# binarybox.net
KiCad netlist of a schematic drawn in EAGLE
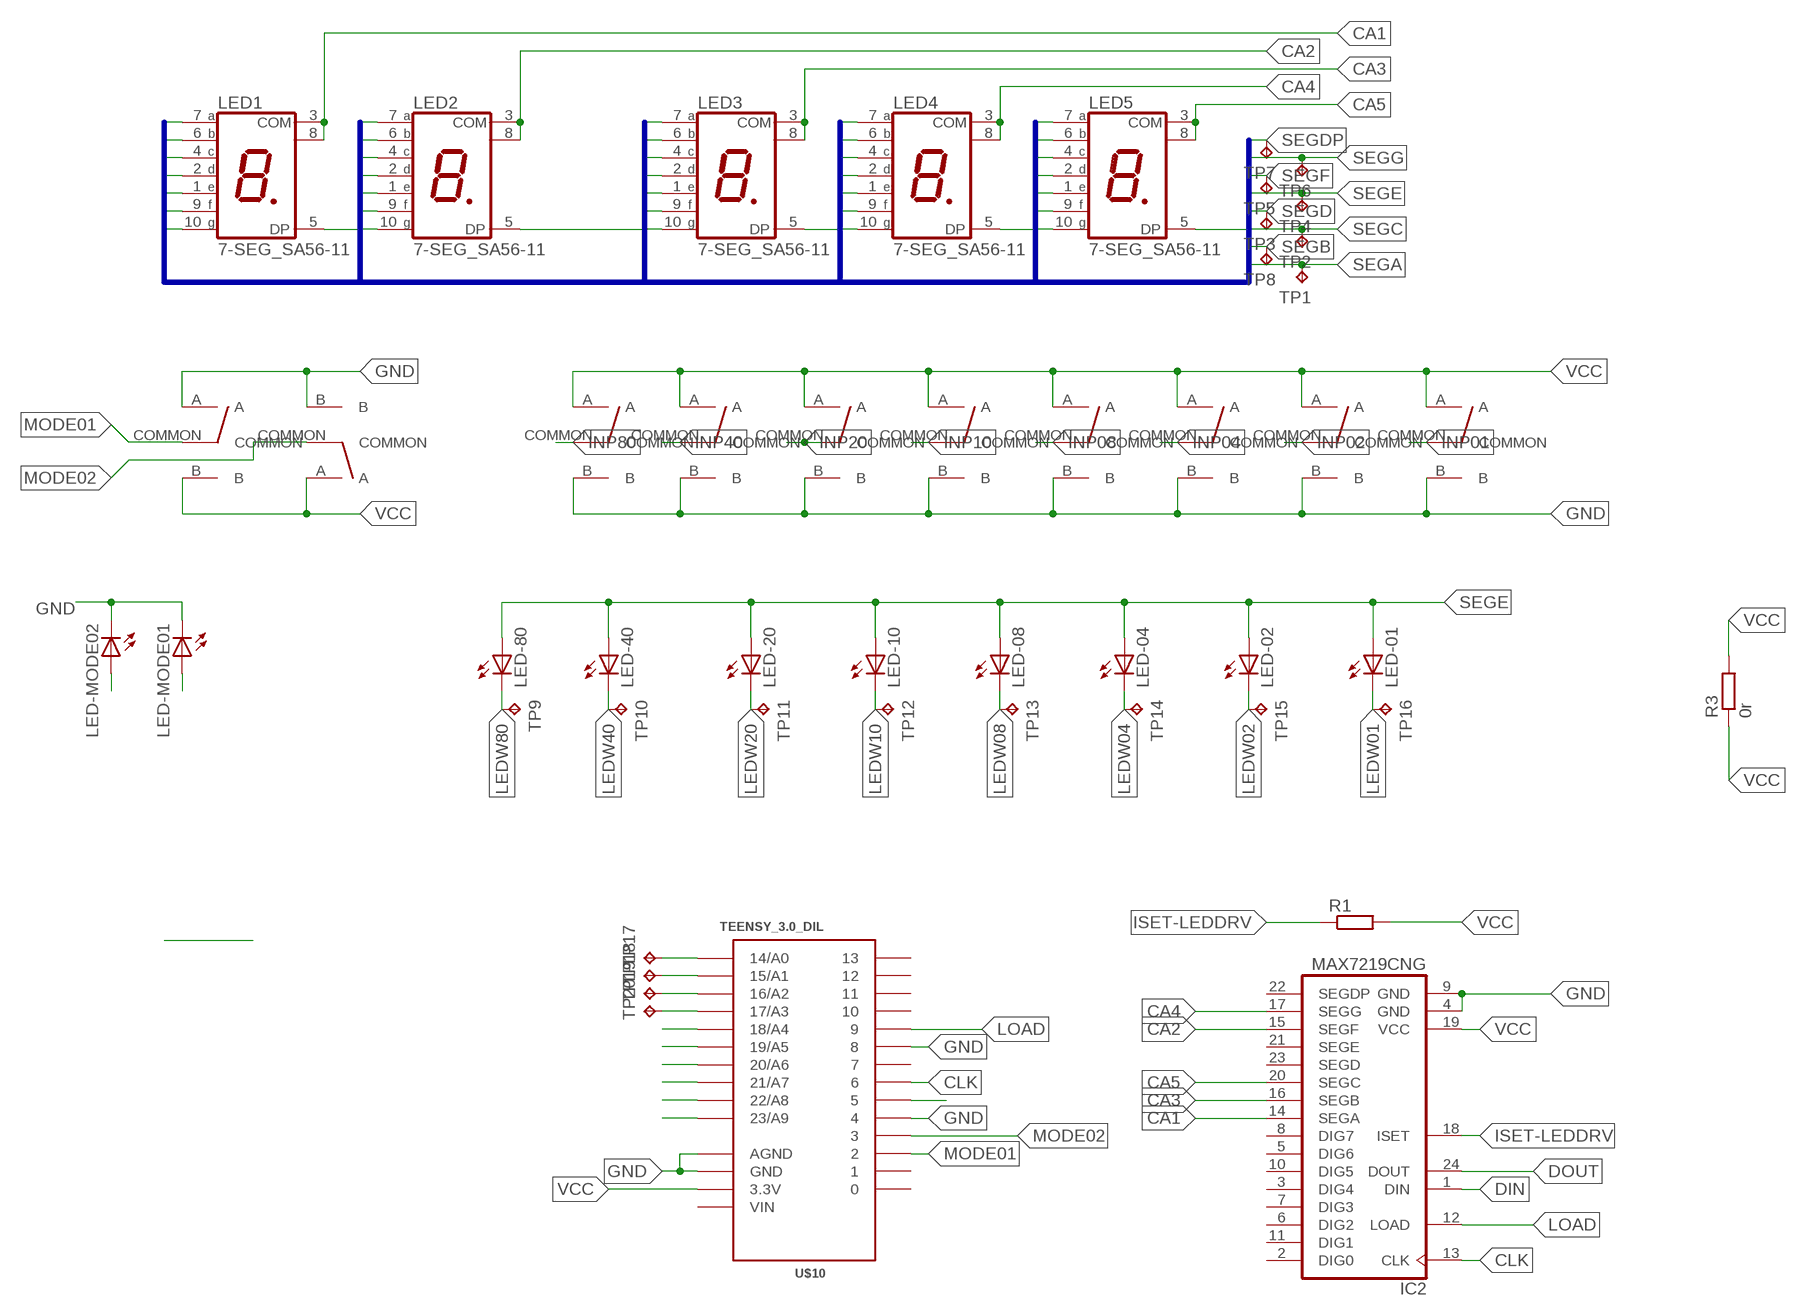
[diagram p0: schematic, sheet 1]

(export (version "E")
  (design (tool "Eeschema 10.0.6"))
  (components
    (comp (ref "IC2")
      (value "MAX7219CNG")
      (footprint "eagle-import:DIL24-3")
      (fields (field (name "MF") "MAXIM"))
      (libsource (lib "eagle-import") (part "MAX7219CNG"))
    )
    (comp (ref "LED-01")
      (value "LED5MM")
      (footprint "eagle-import:LED5MM")
      (libsource (lib "eagle-import") (part "LED5MM"))
    )
    (comp (ref "LED-02")
      (value "LED5MM")
      (footprint "eagle-import:LED5MM")
      (libsource (lib "eagle-import") (part "LED5MM"))
    )
    (comp (ref "LED-04")
      (value "LED5MM")
      (footprint "eagle-import:LED5MM")
      (libsource (lib "eagle-import") (part "LED5MM"))
    )
    (comp (ref "LED-08")
      (value "LED5MM")
      (footprint "eagle-import:LED5MM")
      (libsource (lib "eagle-import") (part "LED5MM"))
    )
    (comp (ref "LED-10")
      (value "LED5MM")
      (footprint "eagle-import:LED5MM")
      (libsource (lib "eagle-import") (part "LED5MM"))
    )
    (comp (ref "LED-20")
      (value "LED5MM")
      (footprint "eagle-import:LED5MM")
      (libsource (lib "eagle-import") (part "LED5MM"))
    )
    (comp (ref "LED-40")
      (value "LED5MM")
      (footprint "eagle-import:LED5MM")
      (libsource (lib "eagle-import") (part "LED5MM"))
    )
    (comp (ref "LED-80")
      (value "LED5MM")
      (footprint "eagle-import:LED5MM")
      (libsource (lib "eagle-import") (part "LED5MM"))
    )
    (comp (ref "LED-MODE01")
      (value "LED5MM")
      (footprint "eagle-import:LED5MM")
      (libsource (lib "eagle-import") (part "LED5MM"))
    )
    (comp (ref "LED-MODE02")
      (value "LED5MM")
      (footprint "eagle-import:LED5MM")
      (libsource (lib "eagle-import") (part "LED5MM"))
    )
    (comp (ref "LED1")
      (value "7-SEG_SA56-11")
      (footprint "eagle-import:SA56-11")
      (libsource (lib "eagle-import") (part "7-SEG_SA56-11"))
    )
    (comp (ref "LED2")
      (value "7-SEG_SA56-11")
      (footprint "eagle-import:SA56-11")
      (libsource (lib "eagle-import") (part "7-SEG_SA56-11"))
    )
    (comp (ref "LED3")
      (value "7-SEG_SA56-11")
      (footprint "eagle-import:SA56-11")
      (libsource (lib "eagle-import") (part "7-SEG_SA56-11"))
    )
    (comp (ref "LED4")
      (value "7-SEG_SA56-11")
      (footprint "eagle-import:SA56-11")
      (libsource (lib "eagle-import") (part "7-SEG_SA56-11"))
    )
    (comp (ref "LED5")
      (value "7-SEG_SA56-11")
      (footprint "eagle-import:SA56-11")
      (libsource (lib "eagle-import") (part "7-SEG_SA56-11"))
    )
    (comp (ref "R1")
      (value "R-EU_0207/10")
      (footprint "eagle-import:0207_10")
      (libsource (lib "eagle-import") (part "R-EU_0207/10"))
    )
    (comp (ref "R3")
      (value "0r")
      (footprint "eagle-import:0207_10")
      (libsource (lib "eagle-import") (part "R-EU_0207/10"))
    )
    (comp (ref "TP1")
      (value "TPB1,27")
      (footprint "eagle-import:B1,27")
      (libsource (lib "eagle-import") (part "TPB1,27"))
    )
    (comp (ref "TP2")
      (value "TPB1,27")
      (footprint "eagle-import:B1,27")
      (libsource (lib "eagle-import") (part "TPB1,27"))
    )
    (comp (ref "TP3")
      (value "TPB1,27")
      (footprint "eagle-import:B1,27")
      (libsource (lib "eagle-import") (part "TPB1,27"))
    )
    (comp (ref "TP4")
      (value "TPB1,27")
      (footprint "eagle-import:B1,27")
      (libsource (lib "eagle-import") (part "TPB1,27"))
    )
    (comp (ref "TP5")
      (value "TPB1,27")
      (footprint "eagle-import:B1,27")
      (libsource (lib "eagle-import") (part "TPB1,27"))
    )
    (comp (ref "TP6")
      (value "TPB1,27")
      (footprint "eagle-import:B1,27")
      (libsource (lib "eagle-import") (part "TPB1,27"))
    )
    (comp (ref "TP7")
      (value "TPB1,27")
      (footprint "eagle-import:B1,27")
      (libsource (lib "eagle-import") (part "TPB1,27"))
    )
    (comp (ref "TP8")
      (value "TPB1,27")
      (footprint "eagle-import:B1,27")
      (libsource (lib "eagle-import") (part "TPB1,27"))
    )
    (comp (ref "TP9")
      (value "TPB1,27")
      (footprint "eagle-import:B1,27")
      (libsource (lib "eagle-import") (part "TPB1,27"))
    )
    (comp (ref "TP10")
      (value "TPB1,27")
      (footprint "eagle-import:B1,27")
      (libsource (lib "eagle-import") (part "TPB1,27"))
    )
    (comp (ref "TP11")
      (value "TPB1,27")
      (footprint "eagle-import:B1,27")
      (libsource (lib "eagle-import") (part "TPB1,27"))
    )
    (comp (ref "TP12")
      (value "TPB1,27")
      (footprint "eagle-import:B1,27")
      (libsource (lib "eagle-import") (part "TPB1,27"))
    )
    (comp (ref "TP13")
      (value "TPB1,27")
      (footprint "eagle-import:B1,27")
      (libsource (lib "eagle-import") (part "TPB1,27"))
    )
    (comp (ref "TP14")
      (value "TPB1,27")
      (footprint "eagle-import:B1,27")
      (libsource (lib "eagle-import") (part "TPB1,27"))
    )
    (comp (ref "TP15")
      (value "TPB1,27")
      (footprint "eagle-import:B1,27")
      (libsource (lib "eagle-import") (part "TPB1,27"))
    )
    (comp (ref "TP16")
      (value "TPB1,27")
      (footprint "eagle-import:B1,27")
      (libsource (lib "eagle-import") (part "TPB1,27"))
    )
    (comp (ref "TP17")
      (value "TPB1,27")
      (footprint "eagle-import:B1,27")
      (libsource (lib "eagle-import") (part "TPB1,27"))
    )
    (comp (ref "TP18")
      (value "TPB1,27")
      (footprint "eagle-import:B1,27")
      (libsource (lib "eagle-import") (part "TPB1,27"))
    )
    (comp (ref "TP19")
      (value "TPB1,27")
      (footprint "eagle-import:B1,27")
      (libsource (lib "eagle-import") (part "TPB1,27"))
    )
    (comp (ref "TP20")
      (value "TPB1,27")
      (footprint "eagle-import:B1,27")
      (libsource (lib "eagle-import") (part "TPB1,27"))
    )
    (comp (ref "U$1")
      (value "ARROW-AB-SWITCH")
      (footprint "eagle-import:333-333")
      (libsource (lib "eagle-import") (part "ARROW-AB-SWITCH"))
    )
    (comp (ref "U$2")
      (value "ARROW-AB-SWITCH")
      (footprint "eagle-import:333-333")
      (libsource (lib "eagle-import") (part "ARROW-AB-SWITCH"))
    )
    (comp (ref "U$3")
      (value "ARROW-AB-SWITCH")
      (footprint "eagle-import:333-333")
      (libsource (lib "eagle-import") (part "ARROW-AB-SWITCH"))
    )
    (comp (ref "U$4")
      (value "ARROW-AB-SWITCH")
      (footprint "eagle-import:333-333")
      (libsource (lib "eagle-import") (part "ARROW-AB-SWITCH"))
    )
    (comp (ref "U$5")
      (value "ARROW-AB-SWITCH")
      (footprint "eagle-import:333-333")
      (libsource (lib "eagle-import") (part "ARROW-AB-SWITCH"))
    )
    (comp (ref "U$6")
      (value "ARROW-AB-SWITCH")
      (footprint "eagle-import:333-333")
      (libsource (lib "eagle-import") (part "ARROW-AB-SWITCH"))
    )
    (comp (ref "U$7")
      (value "ARROW-AB-SWITCH")
      (footprint "eagle-import:333-333")
      (libsource (lib "eagle-import") (part "ARROW-AB-SWITCH"))
    )
    (comp (ref "U$8")
      (value "ARROW-AB-SWITCH")
      (footprint "eagle-import:333-333")
      (libsource (lib "eagle-import") (part "ARROW-AB-SWITCH"))
    )
    (comp (ref "U$10")
      (value "TEENSY_3.0_DIL")
      (footprint "eagle-import:TEENSY3-DIL")
      (libsource (lib "eagle-import") (part "TEENSY_3.0_DIL"))
    )
    (comp (ref "U$11")
      (value "ARROW-AB-SWITCH")
      (footprint "eagle-import:333-333")
      (libsource (lib "eagle-import") (part "ARROW-AB-SWITCH"))
    )
    (comp (ref "U$13")
      (value "ARROW-AB-SWITCH")
      (footprint "eagle-import:333-333")
      (libsource (lib "eagle-import") (part "ARROW-AB-SWITCH"))
    )
  )
  (nets
    (net (code "1") (name "/VIN") (class "Default")
      (node (ref "U$10") (pin "VIN") (pinfunction "VIN_VIN") (pintype "power_in"))
    )
    (net (code "2") (name "CA1") (class "Default")
      (node (ref "IC2") (pin "14") (pinfunction "SEGA_14") (pintype "output"))
      (node (ref "LED1") (pin "3") (pinfunction "COM_3") (pintype "passive"))
      (node (ref "LED1") (pin "8") (pinfunction "COM_8") (pintype "passive"))
    )
    (net (code "3") (name "CA2") (class "Default")
      (node (ref "IC2") (pin "15") (pinfunction "SEGF_15") (pintype "output"))
      (node (ref "LED2") (pin "3") (pinfunction "COM_3") (pintype "passive"))
      (node (ref "LED2") (pin "8") (pinfunction "COM_8") (pintype "passive"))
    )
    (net (code "4") (name "CA3") (class "Default")
      (node (ref "IC2") (pin "16") (pinfunction "SEGB_16") (pintype "output"))
      (node (ref "LED3") (pin "3") (pinfunction "COM_3") (pintype "passive"))
      (node (ref "LED3") (pin "8") (pinfunction "COM_8") (pintype "passive"))
    )
    (net (code "5") (name "CA4") (class "Default")
      (node (ref "IC2") (pin "17") (pinfunction "SEGG_17") (pintype "output"))
      (node (ref "LED4") (pin "3") (pinfunction "COM_3") (pintype "passive"))
      (node (ref "LED4") (pin "8") (pinfunction "COM_8") (pintype "passive"))
    )
    (net (code "6") (name "CA5") (class "Default")
      (node (ref "IC2") (pin "20") (pinfunction "SEGC_20") (pintype "output"))
      (node (ref "LED5") (pin "3") (pinfunction "COM_3") (pintype "passive"))
      (node (ref "LED5") (pin "8") (pinfunction "COM_8") (pintype "passive"))
    )
    (net (code "7") (name "CLK") (class "Default")
      (node (ref "IC2") (pin "13") (pinfunction "CLK_13") (pintype "input"))
      (node (ref "U$10") (pin "6") (pinfunction "6_6") (pintype "bidirectional"))
    )
    (net (code "8") (name "DIN") (class "Default")
      (node (ref "IC2") (pin "1") (pinfunction "DIN_1") (pintype "input"))
      (node (ref "U$10") (pin "5") (pinfunction "5_5") (pintype "bidirectional"))
    )
    (net (code "9") (name "DOUT") (class "Default")
      (node (ref "IC2") (pin "24") (pinfunction "DOUT_24") (pintype "output"))
    )
    (net (code "10") (name "GND") (class "Default")
      (node (ref "IC2") (pin "4") (pinfunction "GND_4") (pintype "power_in"))
      (node (ref "IC2") (pin "9") (pinfunction "GND_9") (pintype "power_in"))
      (node (ref "LED-MODE01") (pin "K") (pinfunction "C_K") (pintype "passive"))
      (node (ref "LED-MODE02") (pin "K") (pinfunction "C_K") (pintype "passive"))
      (node (ref "U$1") (pin "B") (pinfunction "B_B") (pintype "bidirectional"))
      (node (ref "U$10") (pin "4") (pinfunction "4_4") (pintype "bidirectional"))
      (node (ref "U$10") (pin "8") (pinfunction "8_8") (pintype "bidirectional"))
      (node (ref "U$10") (pin "AGND") (pinfunction "AGND_AGND") (pintype "power_in"))
      (node (ref "U$10") (pin "GND") (pinfunction "GND_GND") (pintype "power_in"))
      (node (ref "U$11") (pin "A") (pinfunction "A_A") (pintype "bidirectional"))
      (node (ref "U$13") (pin "B") (pinfunction "B_B") (pintype "bidirectional"))
      (node (ref "U$2") (pin "B") (pinfunction "B_B") (pintype "bidirectional"))
      (node (ref "U$3") (pin "B") (pinfunction "B_B") (pintype "bidirectional"))
      (node (ref "U$4") (pin "B") (pinfunction "B_B") (pintype "bidirectional"))
      (node (ref "U$5") (pin "B") (pinfunction "B_B") (pintype "bidirectional"))
      (node (ref "U$6") (pin "B") (pinfunction "B_B") (pintype "bidirectional"))
      (node (ref "U$7") (pin "B") (pinfunction "B_B") (pintype "bidirectional"))
      (node (ref "U$8") (pin "B") (pinfunction "B_B") (pintype "bidirectional"))
    )
    (net (code "11") (name "INP01") (class "Default")
      (node (ref "U$8") (pin "COMMON") (pinfunction "COMMON_COMMON") (pintype "bidirectional"))
    )
    (net (code "12") (name "INP02") (class "Default")
      (node (ref "U$7") (pin "COMMON") (pinfunction "COMMON_COMMON") (pintype "bidirectional"))
    )
    (net (code "13") (name "INP04") (class "Default")
      (node (ref "U$6") (pin "COMMON") (pinfunction "COMMON_COMMON") (pintype "bidirectional"))
    )
    (net (code "14") (name "INP08") (class "Default")
      (node (ref "U$5") (pin "COMMON") (pinfunction "COMMON_COMMON") (pintype "bidirectional"))
    )
    (net (code "15") (name "INP10") (class "Default")
      (node (ref "U$4") (pin "COMMON") (pinfunction "COMMON_COMMON") (pintype "bidirectional"))
    )
    (net (code "16") (name "INP20") (class "Default")
      (node (ref "U$3") (pin "COMMON") (pinfunction "COMMON_COMMON") (pintype "bidirectional"))
    )
    (net (code "17") (name "INP40") (class "Default")
      (node (ref "U$2") (pin "COMMON") (pinfunction "COMMON_COMMON") (pintype "bidirectional"))
    )
    (net (code "18") (name "INP80") (class "Default")
      (node (ref "U$1") (pin "COMMON") (pinfunction "COMMON_COMMON") (pintype "bidirectional"))
    )
    (net (code "19") (name "ISET-LEDDRV") (class "Default")
      (node (ref "IC2") (pin "18") (pinfunction "ISET_18") (pintype "input"))
      (node (ref "R1") (pin "1") (pinfunction "1_1") (pintype "passive"))
    )
    (net (code "20") (name "LEDW01") (class "Default")
      (node (ref "LED-01") (pin "K") (pinfunction "C_K") (pintype "passive"))
      (node (ref "TP16") (pin "TP") (pinfunction "TP_TP") (pintype "input"))
    )
    (net (code "21") (name "LEDW02") (class "Default")
      (node (ref "LED-02") (pin "K") (pinfunction "C_K") (pintype "passive"))
      (node (ref "TP15") (pin "TP") (pinfunction "TP_TP") (pintype "input"))
    )
    (net (code "22") (name "LEDW04") (class "Default")
      (node (ref "LED-04") (pin "K") (pinfunction "C_K") (pintype "passive"))
      (node (ref "TP14") (pin "TP") (pinfunction "TP_TP") (pintype "input"))
    )
    (net (code "23") (name "LEDW08") (class "Default")
      (node (ref "LED-08") (pin "K") (pinfunction "C_K") (pintype "passive"))
      (node (ref "TP13") (pin "TP") (pinfunction "TP_TP") (pintype "input"))
    )
    (net (code "24") (name "LEDW10") (class "Default")
      (node (ref "LED-10") (pin "K") (pinfunction "C_K") (pintype "passive"))
      (node (ref "TP12") (pin "TP") (pinfunction "TP_TP") (pintype "input"))
    )
    (net (code "25") (name "LEDW20") (class "Default")
      (node (ref "LED-20") (pin "K") (pinfunction "C_K") (pintype "passive"))
      (node (ref "TP11") (pin "TP") (pinfunction "TP_TP") (pintype "input"))
    )
    (net (code "26") (name "LEDW40") (class "Default")
      (node (ref "LED-40") (pin "K") (pinfunction "C_K") (pintype "passive"))
      (node (ref "TP10") (pin "TP") (pinfunction "TP_TP") (pintype "input"))
    )
    (net (code "27") (name "LEDW80") (class "Default")
      (node (ref "LED-80") (pin "K") (pinfunction "C_K") (pintype "passive"))
      (node (ref "TP9") (pin "TP") (pinfunction "TP_TP") (pintype "input"))
    )
    (net (code "28") (name "LOAD") (class "Default")
      (node (ref "IC2") (pin "12") (pinfunction "LOAD_12") (pintype "input"))
      (node (ref "U$10") (pin "9") (pinfunction "9_9") (pintype "bidirectional"))
    )
    (net (code "29") (name "MODE01") (class "Default")
      (node (ref "U$10") (pin "2") (pinfunction "2_2") (pintype "bidirectional"))
      (node (ref "U$11") (pin "COMMON") (pinfunction "COMMON_COMMON") (pintype "bidirectional"))
    )
    (net (code "30") (name "MODE02") (class "Default")
      (node (ref "U$10") (pin "3") (pinfunction "3_3") (pintype "bidirectional"))
      (node (ref "U$13") (pin "COMMON") (pinfunction "COMMON_COMMON") (pintype "bidirectional"))
    )
    (net (code "31") (name "Net-(TP17-PadTP)") (class "Default")
      (node (ref "TP17") (pin "TP") (pinfunction "TP_TP") (pintype "input"))
      (node (ref "U$10") (pin "14/A0") (pinfunction "14/A0_14/A0") (pintype "bidirectional"))
    )
    (net (code "32") (name "Net-(TP18-PadTP)") (class "Default")
      (node (ref "TP18") (pin "TP") (pinfunction "TP_TP") (pintype "input"))
      (node (ref "U$10") (pin "15/A1") (pinfunction "15/A1_15/A1") (pintype "bidirectional"))
    )
    (net (code "33") (name "Net-(TP19-PadTP)") (class "Default")
      (node (ref "TP19") (pin "TP") (pinfunction "TP_TP") (pintype "input"))
      (node (ref "U$10") (pin "16/A2") (pinfunction "16/A2_16/A2") (pintype "bidirectional"))
    )
    (net (code "34") (name "Net-(TP20-PadTP)") (class "Default")
      (node (ref "TP20") (pin "TP") (pinfunction "TP_TP") (pintype "input"))
      (node (ref "U$10") (pin "17/A3") (pinfunction "17/A3_17/A3") (pintype "bidirectional"))
    )
    (net (code "35") (name "SEGA") (class "Default")
      (node (ref "LED1") (pin "7") (pinfunction "A_7") (pintype "passive"))
      (node (ref "LED2") (pin "7") (pinfunction "A_7") (pintype "passive"))
      (node (ref "LED3") (pin "7") (pinfunction "A_7") (pintype "passive"))
      (node (ref "LED4") (pin "7") (pinfunction "A_7") (pintype "passive"))
      (node (ref "LED5") (pin "7") (pinfunction "A_7") (pintype "passive"))
      (node (ref "TP1") (pin "TP") (pinfunction "TP_TP") (pintype "input"))
    )
    (net (code "36") (name "SEGB") (class "Default")
      (node (ref "LED1") (pin "6") (pinfunction "B_6") (pintype "passive"))
      (node (ref "LED2") (pin "6") (pinfunction "B_6") (pintype "passive"))
      (node (ref "LED3") (pin "6") (pinfunction "B_6") (pintype "passive"))
      (node (ref "LED4") (pin "6") (pinfunction "B_6") (pintype "passive"))
      (node (ref "LED5") (pin "6") (pinfunction "B_6") (pintype "passive"))
      (node (ref "TP8") (pin "TP") (pinfunction "TP_TP") (pintype "input"))
    )
    (net (code "37") (name "SEGC") (class "Default")
      (node (ref "LED1") (pin "4") (pinfunction "C_4") (pintype "passive"))
      (node (ref "LED2") (pin "4") (pinfunction "C_4") (pintype "passive"))
      (node (ref "LED3") (pin "4") (pinfunction "C_4") (pintype "passive"))
      (node (ref "LED4") (pin "4") (pinfunction "C_4") (pintype "passive"))
      (node (ref "LED5") (pin "4") (pinfunction "C_4") (pintype "passive"))
      (node (ref "TP2") (pin "TP") (pinfunction "TP_TP") (pintype "input"))
    )
    (net (code "38") (name "SEGD") (class "Default")
      (node (ref "LED1") (pin "2") (pinfunction "D_2") (pintype "passive"))
      (node (ref "LED2") (pin "2") (pinfunction "D_2") (pintype "passive"))
      (node (ref "LED3") (pin "2") (pinfunction "D_2") (pintype "passive"))
      (node (ref "LED4") (pin "2") (pinfunction "D_2") (pintype "passive"))
      (node (ref "LED5") (pin "2") (pinfunction "D_2") (pintype "passive"))
      (node (ref "TP3") (pin "TP") (pinfunction "TP_TP") (pintype "input"))
    )
    (net (code "39") (name "SEGDP") (class "Default")
      (node (ref "LED1") (pin "5") (pinfunction "DP_5") (pintype "passive"))
      (node (ref "LED2") (pin "5") (pinfunction "DP_5") (pintype "passive"))
      (node (ref "LED3") (pin "5") (pinfunction "DP_5") (pintype "passive"))
      (node (ref "LED4") (pin "5") (pinfunction "DP_5") (pintype "passive"))
      (node (ref "LED5") (pin "5") (pinfunction "DP_5") (pintype "passive"))
      (node (ref "TP7") (pin "TP") (pinfunction "TP_TP") (pintype "input"))
    )
    (net (code "40") (name "SEGE") (class "Default")
      (node (ref "LED-01") (pin "A") (pinfunction "A_A") (pintype "passive"))
      (node (ref "LED-02") (pin "A") (pinfunction "A_A") (pintype "passive"))
      (node (ref "LED-04") (pin "A") (pinfunction "A_A") (pintype "passive"))
      (node (ref "LED-08") (pin "A") (pinfunction "A_A") (pintype "passive"))
      (node (ref "LED-10") (pin "A") (pinfunction "A_A") (pintype "passive"))
      (node (ref "LED-20") (pin "A") (pinfunction "A_A") (pintype "passive"))
      (node (ref "LED-40") (pin "A") (pinfunction "A_A") (pintype "passive"))
      (node (ref "LED-80") (pin "A") (pinfunction "A_A") (pintype "passive"))
      (node (ref "LED1") (pin "1") (pinfunction "E_1") (pintype "passive"))
      (node (ref "LED2") (pin "1") (pinfunction "E_1") (pintype "passive"))
      (node (ref "LED3") (pin "1") (pinfunction "E_1") (pintype "passive"))
      (node (ref "LED4") (pin "1") (pinfunction "E_1") (pintype "passive"))
      (node (ref "LED5") (pin "1") (pinfunction "E_1") (pintype "passive"))
      (node (ref "TP4") (pin "TP") (pinfunction "TP_TP") (pintype "input"))
    )
    (net (code "41") (name "SEGF") (class "Default")
      (node (ref "LED1") (pin "9") (pinfunction "F_9") (pintype "passive"))
      (node (ref "LED2") (pin "9") (pinfunction "F_9") (pintype "passive"))
      (node (ref "LED3") (pin "9") (pinfunction "F_9") (pintype "passive"))
      (node (ref "LED4") (pin "9") (pinfunction "F_9") (pintype "passive"))
      (node (ref "LED5") (pin "9") (pinfunction "F_9") (pintype "passive"))
      (node (ref "TP5") (pin "TP") (pinfunction "TP_TP") (pintype "input"))
    )
    (net (code "42") (name "SEGG") (class "Default")
      (node (ref "LED1") (pin "10") (pinfunction "G_10") (pintype "passive"))
      (node (ref "LED2") (pin "10") (pinfunction "G_10") (pintype "passive"))
      (node (ref "LED3") (pin "10") (pinfunction "G_10") (pintype "passive"))
      (node (ref "LED4") (pin "10") (pinfunction "G_10") (pintype "passive"))
      (node (ref "LED5") (pin "10") (pinfunction "G_10") (pintype "passive"))
      (node (ref "TP6") (pin "TP") (pinfunction "TP_TP") (pintype "input"))
    )
    (net (code "43") (name "VCC") (class "Default")
      (node (ref "IC2") (pin "19") (pinfunction "VCC_19") (pintype "power_in"))
      (node (ref "R1") (pin "2") (pinfunction "2_2") (pintype "passive"))
      (node (ref "R3") (pin "1") (pinfunction "1_1") (pintype "passive"))
      (node (ref "R3") (pin "2") (pinfunction "2_2") (pintype "passive"))
      (node (ref "U$1") (pin "A") (pinfunction "A_A") (pintype "bidirectional"))
      (node (ref "U$10") (pin "3.3V") (pinfunction "3.3V_3.3V") (pintype "power_in"))
      (node (ref "U$11") (pin "B") (pinfunction "B_B") (pintype "bidirectional"))
      (node (ref "U$13") (pin "A") (pinfunction "A_A") (pintype "bidirectional"))
      (node (ref "U$2") (pin "A") (pinfunction "A_A") (pintype "bidirectional"))
      (node (ref "U$3") (pin "A") (pinfunction "A_A") (pintype "bidirectional"))
      (node (ref "U$4") (pin "A") (pinfunction "A_A") (pintype "bidirectional"))
      (node (ref "U$5") (pin "A") (pinfunction "A_A") (pintype "bidirectional"))
      (node (ref "U$6") (pin "A") (pinfunction "A_A") (pintype "bidirectional"))
      (node (ref "U$7") (pin "A") (pinfunction "A_A") (pintype "bidirectional"))
      (node (ref "U$8") (pin "A") (pinfunction "A_A") (pintype "bidirectional"))
    )
    (net (code "44") (name "unconnected-(IC2-DIG0-Pad2)") (class "Default")
      (node (ref "IC2") (pin "2") (pinfunction "DIG0_2") (pintype "output"))
    )
    (net (code "45") (name "unconnected-(IC2-DIG1-Pad11)") (class "Default")
      (node (ref "IC2") (pin "11") (pinfunction "DIG1_11") (pintype "output"))
    )
    (net (code "46") (name "unconnected-(IC2-DIG2-Pad6)") (class "Default")
      (node (ref "IC2") (pin "6") (pinfunction "DIG2_6") (pintype "output"))
    )
    (net (code "47") (name "unconnected-(IC2-DIG3-Pad7)") (class "Default")
      (node (ref "IC2") (pin "7") (pinfunction "DIG3_7") (pintype "output"))
    )
    (net (code "48") (name "unconnected-(IC2-DIG4-Pad3)") (class "Default")
      (node (ref "IC2") (pin "3") (pinfunction "DIG4_3") (pintype "output"))
    )
    (net (code "49") (name "unconnected-(IC2-DIG5-Pad10)") (class "Default")
      (node (ref "IC2") (pin "10") (pinfunction "DIG5_10") (pintype "output"))
    )
    (net (code "50") (name "unconnected-(IC2-DIG6-Pad5)") (class "Default")
      (node (ref "IC2") (pin "5") (pinfunction "DIG6_5") (pintype "output"))
    )
    (net (code "51") (name "unconnected-(IC2-DIG7-Pad8)") (class "Default")
      (node (ref "IC2") (pin "8") (pinfunction "DIG7_8") (pintype "output"))
    )
    (net (code "52") (name "unconnected-(IC2-SEGD-Pad23)") (class "Default")
      (node (ref "IC2") (pin "23") (pinfunction "SEGD_23") (pintype "output"))
    )
    (net (code "53") (name "unconnected-(IC2-SEGDP-Pad22)") (class "Default")
      (node (ref "IC2") (pin "22") (pinfunction "SEGDP_22") (pintype "output"))
    )
    (net (code "54") (name "unconnected-(IC2-SEGE-Pad21)") (class "Default")
      (node (ref "IC2") (pin "21") (pinfunction "SEGE_21") (pintype "output"))
    )
    (net (code "55") (name "unconnected-(LED-MODE01-PadA)") (class "Default")
      (node (ref "LED-MODE01") (pin "A") (pinfunction "A_A") (pintype "passive"))
    )
    (net (code "56") (name "unconnected-(LED-MODE02-PadA)") (class "Default")
      (node (ref "LED-MODE02") (pin "A") (pinfunction "A_A") (pintype "passive"))
    )
    (net (code "57") (name "unconnected-(U$10-Pad0)") (class "Default")
      (node (ref "U$10") (pin "0") (pinfunction "0_0") (pintype "bidirectional"))
    )
    (net (code "58") (name "unconnected-(U$10-Pad1)") (class "Default")
      (node (ref "U$10") (pin "1") (pinfunction "1_1") (pintype "bidirectional"))
    )
    (net (code "59") (name "unconnected-(U$10-Pad7)") (class "Default")
      (node (ref "U$10") (pin "7") (pinfunction "7_7") (pintype "bidirectional"))
    )
    (net (code "60") (name "unconnected-(U$10-Pad10)") (class "Default")
      (node (ref "U$10") (pin "10") (pinfunction "10_10") (pintype "bidirectional"))
    )
    (net (code "61") (name "unconnected-(U$10-Pad11)") (class "Default")
      (node (ref "U$10") (pin "11") (pinfunction "11_11") (pintype "bidirectional"))
    )
    (net (code "62") (name "unconnected-(U$10-Pad12)") (class "Default")
      (node (ref "U$10") (pin "12") (pinfunction "12_12") (pintype "bidirectional"))
    )
    (net (code "63") (name "unconnected-(U$10-Pad13)") (class "Default")
      (node (ref "U$10") (pin "13") (pinfunction "13_13") (pintype "bidirectional"))
    )
    (net (code "64") (name "unconnected-(U$10-Pad18{slash}A4)") (class "Default")
      (node (ref "U$10") (pin "18/A4") (pinfunction "18/A4_18/A4") (pintype "bidirectional"))
    )
    (net (code "65") (name "unconnected-(U$10-Pad19{slash}A5)") (class "Default")
      (node (ref "U$10") (pin "19/A5") (pinfunction "19/A5_19/A5") (pintype "bidirectional"))
    )
    (net (code "66") (name "unconnected-(U$10-Pad20{slash}A6)") (class "Default")
      (node (ref "U$10") (pin "20/A6") (pinfunction "20/A6_20/A6") (pintype "bidirectional"))
    )
    (net (code "67") (name "unconnected-(U$10-Pad21{slash}A7)") (class "Default")
      (node (ref "U$10") (pin "21/A7") (pinfunction "21/A7_21/A7") (pintype "bidirectional"))
    )
    (net (code "68") (name "unconnected-(U$10-Pad22{slash}A8)") (class "Default")
      (node (ref "U$10") (pin "22/A8") (pinfunction "22/A8_22/A8") (pintype "bidirectional"))
    )
    (net (code "69") (name "unconnected-(U$10-Pad23{slash}A9)") (class "Default")
      (node (ref "U$10") (pin "23/A9") (pinfunction "23/A9_23/A9") (pintype "bidirectional"))
    )
  )
)
